# Sheet2.net
KiCad netlist of a schematic drawn in Altium Designer
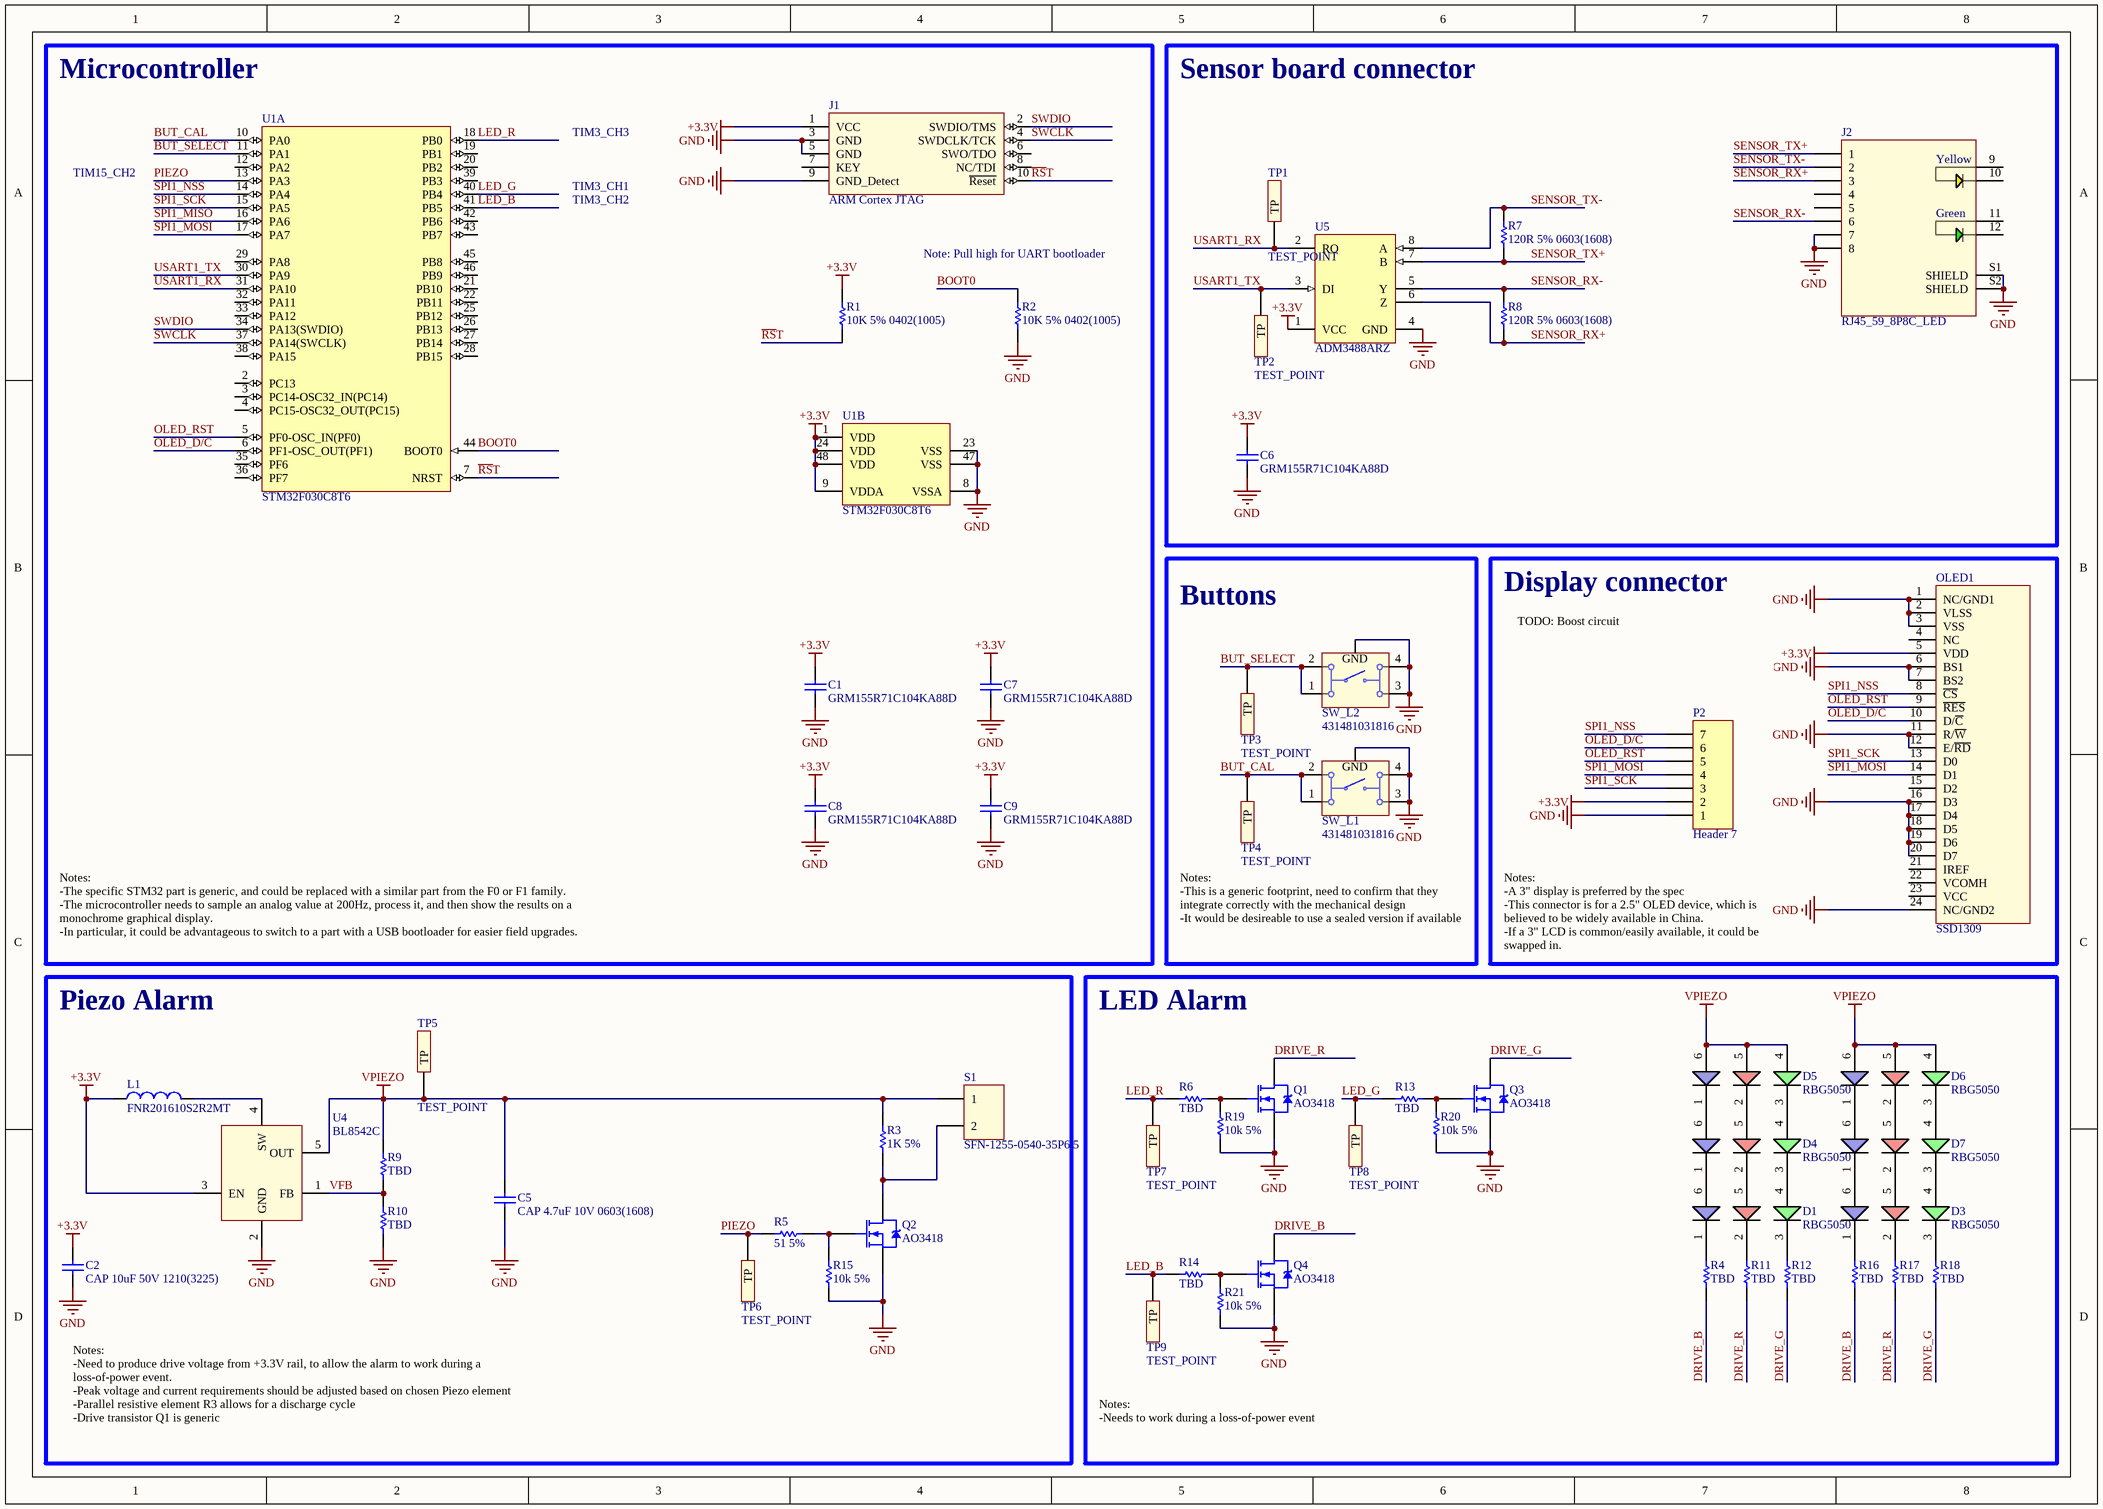
[diagram p0: Sheet2.SchDoc]

(export (version "E")
  (design (tool "Eeschema 10.0.6"))
  (components
    (comp (ref "C1")
      (value "GRM155R71C104KA88D")
      (footprint "CAPC1005X55X25ML05T10")
      (description "Chip Capacitor, 0.1 uF, +/- 10%, 16 V, -55 to 125 degC, 0402 (1005 Metric), RoHS, Tape and Reel")
      (fields (field (name "VOLTAGE") "16V") (field (name "TOLERANCE") "10%"))
      (libsource (lib "Altium Content Vault") (part "CAP-NP-2"))
    )
    (comp (ref "C2")
      (value "CAP 10uF 50V 1210(3225)")
      (footprint "CAPC1210(3225)190_N")
      (description "CAP 10uF 50V -20% to +80% 1210 (3225 Metric) Thickness 1.9mm SMD")
      (fields (field (name "TOLERANCE") "-20% to +80%"))
      (libsource (lib "Altium Content Vault") (part "CAP"))
    )
    (comp (ref "C5")
      (value "CAP 4.7uF 10V 0603(1608)")
      (footprint "CAPC0603(1608)55_L")
      (description "CAP 4.7uF 10V ±10% 0603 (1608 Metric) Thickness 0.55mm SMD")
      (fields (field (name "TOLERANCE") "Â±10%"))
      (libsource (lib "Altium Content Vault") (part "CAP"))
    )
    (comp (ref "C6")
      (value "GRM155R71C104KA88D")
      (footprint "CAPC1005X55X25ML05T10")
      (description "Chip Capacitor, 0.1 uF, +/- 10%, 16 V, -55 to 125 degC, 0402 (1005 Metric), RoHS, Tape and Reel")
      (fields (field (name "VOLTAGE") "16V") (field (name "TOLERANCE") "10%"))
      (libsource (lib "Altium Content Vault") (part "CAP-NP-2"))
    )
    (comp (ref "C7")
      (value "GRM155R71C104KA88D")
      (footprint "CAPC1005X55X25ML05T10")
      (description "Chip Capacitor, 0.1 uF, +/- 10%, 16 V, -55 to 125 degC, 0402 (1005 Metric), RoHS, Tape and Reel")
      (fields (field (name "VOLTAGE") "16V") (field (name "TOLERANCE") "10%"))
      (libsource (lib "Altium Content Vault") (part "CAP-NP-2"))
    )
    (comp (ref "C8")
      (value "GRM155R71C104KA88D")
      (footprint "CAPC1005X55X25ML05T10")
      (description "Chip Capacitor, 0.1 uF, +/- 10%, 16 V, -55 to 125 degC, 0402 (1005 Metric), RoHS, Tape and Reel")
      (fields (field (name "VOLTAGE") "16V") (field (name "TOLERANCE") "10%"))
      (libsource (lib "Altium Content Vault") (part "CAP-NP-2"))
    )
    (comp (ref "C9")
      (value "GRM155R71C104KA88D")
      (footprint "CAPC1005X55X25ML05T10")
      (description "Chip Capacitor, 0.1 uF, +/- 10%, 16 V, -55 to 125 degC, 0402 (1005 Metric), RoHS, Tape and Reel")
      (fields (field (name "VOLTAGE") "16V") (field (name "TOLERANCE") "10%"))
      (libsource (lib "Altium Content Vault") (part "CAP-NP-2"))
    )
    (comp (ref "D1")
      (value "RBG5050")
      (footprint "5050RGB")
      (description "Generic RGB LED in 5050 package. Note that several variants exist, so check the pinout!")
      (fields (field (name "PARTNUMBER") "Unknown/Generic"))
      (libsource (lib "Blinkinlabs") (part "RBG5050"))
    )
    (comp (ref "D3")
      (value "RBG5050")
      (footprint "5050RGB")
      (description "Generic RGB LED in 5050 package. Note that several variants exist, so check the pinout!")
      (fields (field (name "PARTNUMBER") "Unknown/Generic"))
      (libsource (lib "Blinkinlabs") (part "RBG5050"))
    )
    (comp (ref "D4")
      (value "RBG5050")
      (footprint "5050RGB")
      (description "Generic RGB LED in 5050 package. Note that several variants exist, so check the pinout!")
      (fields (field (name "PARTNUMBER") "Unknown/Generic"))
      (libsource (lib "Blinkinlabs") (part "RBG5050"))
    )
    (comp (ref "D5")
      (value "RBG5050")
      (footprint "5050RGB")
      (description "Generic RGB LED in 5050 package. Note that several variants exist, so check the pinout!")
      (fields (field (name "PARTNUMBER") "Unknown/Generic"))
      (libsource (lib "Blinkinlabs") (part "RBG5050"))
    )
    (comp (ref "D6")
      (value "RBG5050")
      (footprint "5050RGB")
      (description "Generic RGB LED in 5050 package. Note that several variants exist, so check the pinout!")
      (fields (field (name "PARTNUMBER") "Unknown/Generic"))
      (libsource (lib "Blinkinlabs") (part "RBG5050"))
    )
    (comp (ref "D7")
      (value "RBG5050")
      (footprint "5050RGB")
      (description "Generic RGB LED in 5050 package. Note that several variants exist, so check the pinout!")
      (fields (field (name "PARTNUMBER") "Unknown/Generic"))
      (libsource (lib "Blinkinlabs") (part "RBG5050"))
    )
    (comp (ref "J1")
      (value "ARM Cortex JTAG")
      (footprint "1.27mm 2x5 SMD Header")
      (description "Arm Cortex 10-pin JTAG connector")
      (fields (field (name "MANUFACTURER") "Unknown/Generic") (field (name "PARTNUMBER") "unknown/Generic"))
      (libsource (lib "Blinkinlabs") (part "ARM Cortex JTAG"))
    )
    (comp (ref "J2")
      (value "RJ45_59_8P8C_LED")
      (footprint "RJ45_59_8P8C_LED")
      (description "Generic RJ49 jack with LED and without magnetics")
      (fields (field (name "MANUFACTURER") "Unknown/Generic"))
      (libsource (lib "Blinkinlabs") (part "RJ45_59_8P8C_LED"))
    )
    (comp (ref "L1")
      (value "FNR201610S2R2MT")
      (footprint "FNR201610S")
      (description "Wire Wound SMD Power Inductors 2.0×1.6×1.0 2.2uH")
      (libsource (lib "Blinkinlabs") (part "FNR201610S2R2MT"))
    )
    (comp (ref "OLED1")
      (value "SSD1309")
      (description "2.4\" OLED display, 24-pin connector, SSD1309 driver IC")
      (libsource (lib "Blinkinlabs") (part "SSD1309"))
    )
    (comp (ref "P2")
      (value "Header 7")
      (footprint "HDR1X7")
      (description "Header, 7-Pin")
      (fields (field (name "PUBLISHER") "Altium Limited"))
      (libsource (lib "Miscellaneous Connectors") (part "Header 7"))
    )
    (comp (ref "Q1")
      (value "AO3418")
      (footprint "SOT95P280X125-3N")
      (description "30V N-Channel MOSFET")
      (fields (field (name "MANUFACTURER") "Alpha & Omega"))
      (libsource (lib "Blinkinlabs") (part "AO3418"))
    )
    (comp (ref "Q2")
      (value "AO3418")
      (footprint "SOT95P280X125-3N")
      (description "30V N-Channel MOSFET")
      (fields (field (name "MANUFACTURER") "Alpha & Omega"))
      (libsource (lib "Blinkinlabs") (part "AO3418"))
    )
    (comp (ref "Q3")
      (value "AO3418")
      (footprint "SOT95P280X125-3N")
      (description "30V N-Channel MOSFET")
      (fields (field (name "MANUFACTURER") "Alpha & Omega"))
      (libsource (lib "Blinkinlabs") (part "AO3418"))
    )
    (comp (ref "Q4")
      (value "AO3418")
      (footprint "SOT95P280X125-3N")
      (description "30V N-Channel MOSFET")
      (fields (field (name "MANUFACTURER") "Alpha & Omega"))
      (libsource (lib "Blinkinlabs") (part "AO3418"))
    )
    (comp (ref "R1")
      (value "10K 5% 0402(1005)")
      (footprint "RESC0402(1005)_N")
      (description "10K 0.063W 5% 0402 (1005 Metric)  SMD")
      (fields (field (name "TOLERANCE") "5 %") (field (name "POWER") "0.063 W"))
      (libsource (lib "Altium Content Vault") (part "RES"))
    )
    (comp (ref "R2")
      (value "10K 5% 0402(1005)")
      (footprint "RESC0402(1005)_N")
      (description "10K 0.063W 5% 0402 (1005 Metric)  SMD")
      (fields (field (name "TOLERANCE") "5 %") (field (name "POWER") "0.063 W"))
      (libsource (lib "Altium Content Vault") (part "RES"))
    )
    (comp (ref "R3")
      (value "1K 5%")
      (footprint "RESC0402(1005)_N")
      (description "10K 0.063W 5% 0402 (1005 Metric)  SMD")
      (fields (field (name "TOLERANCE") "5 %") (field (name "POWER") "0.063 W"))
      (libsource (lib "Altium Content Vault") (part "RES"))
    )
    (comp (ref "R4")
      (value "TBD")
      (footprint "RESC0402(1005)_N")
      (description "10K 0.063W 5% 0402 (1005 Metric)  SMD")
      (fields (field (name "TOLERANCE") "5 %") (field (name "POWER") "0.063 W"))
      (libsource (lib "Altium Content Vault") (part "RES"))
    )
    (comp (ref "R5")
      (value "51 5%")
      (footprint "RESC0402(1005)_N")
      (description "10K 0.063W 5% 0402 (1005 Metric)  SMD")
      (fields (field (name "TOLERANCE") "5 %") (field (name "POWER") "0.063 W"))
      (libsource (lib "Altium Content Vault") (part "RES"))
    )
    (comp (ref "R6")
      (value "TBD")
      (footprint "RESC0402(1005)_N")
      (description "10K 0.063W 5% 0402 (1005 Metric)  SMD")
      (fields (field (name "TOLERANCE") "5 %") (field (name "POWER") "0.063 W"))
      (libsource (lib "Altium Content Vault") (part "RES"))
    )
    (comp (ref "R7")
      (value "120R 5% 0603(1608)")
      (footprint "RESC0603(1608)_L")
      (description "120R 0.1W 5% 0603 (1608 Metric)  SMD")
      (fields (field (name "POWER") "0.1 W") (field (name "TOLERANCE") "5 %"))
      (libsource (lib "Altium Content Vault") (part "RES"))
    )
    (comp (ref "R8")
      (value "120R 5% 0603(1608)")
      (footprint "RESC0603(1608)_L")
      (description "120R 0.1W 5% 0603 (1608 Metric)  SMD")
      (fields (field (name "POWER") "0.1 W") (field (name "TOLERANCE") "5 %"))
      (libsource (lib "Altium Content Vault") (part "RES"))
    )
    (comp (ref "R9")
      (value "TBD")
      (footprint "RESC0402(1005)_N")
      (description "10K 0.063W 5% 0402 (1005 Metric)  SMD")
      (fields (field (name "TOLERANCE") "5 %") (field (name "POWER") "0.063 W"))
      (libsource (lib "Altium Content Vault") (part "RES"))
    )
    (comp (ref "R10")
      (value "TBD")
      (footprint "RESC0402(1005)_N")
      (description "10K 0.063W 5% 0402 (1005 Metric)  SMD")
      (fields (field (name "TOLERANCE") "5 %") (field (name "POWER") "0.063 W"))
      (libsource (lib "Altium Content Vault") (part "RES"))
    )
    (comp (ref "R11")
      (value "TBD")
      (footprint "RESC0402(1005)_N")
      (description "10K 0.063W 5% 0402 (1005 Metric)  SMD")
      (fields (field (name "TOLERANCE") "5 %") (field (name "POWER") "0.063 W"))
      (libsource (lib "Altium Content Vault") (part "RES"))
    )
    (comp (ref "R12")
      (value "TBD")
      (footprint "RESC0402(1005)_N")
      (description "10K 0.063W 5% 0402 (1005 Metric)  SMD")
      (fields (field (name "TOLERANCE") "5 %") (field (name "POWER") "0.063 W"))
      (libsource (lib "Altium Content Vault") (part "RES"))
    )
    (comp (ref "R13")
      (value "TBD")
      (footprint "RESC0402(1005)_N")
      (description "10K 0.063W 5% 0402 (1005 Metric)  SMD")
      (fields (field (name "TOLERANCE") "5 %") (field (name "POWER") "0.063 W"))
      (libsource (lib "Altium Content Vault") (part "RES"))
    )
    (comp (ref "R14")
      (value "TBD")
      (footprint "RESC0402(1005)_N")
      (description "10K 0.063W 5% 0402 (1005 Metric)  SMD")
      (fields (field (name "TOLERANCE") "5 %") (field (name "POWER") "0.063 W"))
      (libsource (lib "Altium Content Vault") (part "RES"))
    )
    (comp (ref "R15")
      (value "10k 5%")
      (footprint "RESC0402(1005)_N")
      (description "10K 0.063W 5% 0402 (1005 Metric)  SMD")
      (fields (field (name "TOLERANCE") "5 %") (field (name "POWER") "0.063 W"))
      (libsource (lib "Altium Content Vault") (part "RES"))
    )
    (comp (ref "R16")
      (value "TBD")
      (footprint "RESC0402(1005)_N")
      (description "10K 0.063W 5% 0402 (1005 Metric)  SMD")
      (fields (field (name "TOLERANCE") "5 %") (field (name "POWER") "0.063 W"))
      (libsource (lib "Altium Content Vault") (part "RES"))
    )
    (comp (ref "R17")
      (value "TBD")
      (footprint "RESC0402(1005)_N")
      (description "10K 0.063W 5% 0402 (1005 Metric)  SMD")
      (fields (field (name "TOLERANCE") "5 %") (field (name "POWER") "0.063 W"))
      (libsource (lib "Altium Content Vault") (part "RES"))
    )
    (comp (ref "R18")
      (value "TBD")
      (footprint "RESC0402(1005)_N")
      (description "10K 0.063W 5% 0402 (1005 Metric)  SMD")
      (fields (field (name "TOLERANCE") "5 %") (field (name "POWER") "0.063 W"))
      (libsource (lib "Altium Content Vault") (part "RES"))
    )
    (comp (ref "R19")
      (value "10k 5%")
      (footprint "RESC0402(1005)_N")
      (description "10K 0.063W 5% 0402 (1005 Metric)  SMD")
      (fields (field (name "TOLERANCE") "5 %") (field (name "POWER") "0.063 W"))
      (libsource (lib "Altium Content Vault") (part "RES"))
    )
    (comp (ref "R20")
      (value "10k 5%")
      (footprint "RESC0402(1005)_N")
      (description "10K 0.063W 5% 0402 (1005 Metric)  SMD")
      (fields (field (name "TOLERANCE") "5 %") (field (name "POWER") "0.063 W"))
      (libsource (lib "Altium Content Vault") (part "RES"))
    )
    (comp (ref "R21")
      (value "10k 5%")
      (footprint "RESC0402(1005)_N")
      (description "10K 0.063W 5% 0402 (1005 Metric)  SMD")
      (fields (field (name "TOLERANCE") "5 %") (field (name "POWER") "0.063 W"))
      (libsource (lib "Altium Content Vault") (part "RES"))
    )
    (comp (ref "S1")
      (value "SFN-1255-0540-35P6.5")
      (footprint "SFN-1255-0540-35P6.5")
      (description "Piezo Buzzer, 4KHz")
      (fields (field (name "MANUFACTURER") "S&S"))
      (libsource (lib "Blinkinlabs") (part "SFN-1255-0540-35P6.5"))
    )
    (comp (ref "SW_L1")
      (value "431481031816")
      (footprint "431481031816")
      (description "WS-TASV SMD Tact Switch 6X6 mm with ground terminal")
      (fields (field (name "MANUFACTURER") "Wuerth Elektronik"))
      (libsource (lib "Altium Content Vault") (part "WE-TACT-SW-5"))
    )
    (comp (ref "SW_L2")
      (value "431481031816")
      (footprint "431481031816")
      (description "WS-TASV SMD Tact Switch 6X6 mm with ground terminal")
      (fields (field (name "MANUFACTURER") "Wuerth Elektronik"))
      (libsource (lib "Altium Content Vault") (part "WE-TACT-SW-5"))
    )
    (comp (ref "TP1")
      (value "TEST_POINT")
      (footprint "TP-SMD-1mm")
      (description "Test point")
      (libsource (lib "") (part "TEST_POINT_1"))
    )
    (comp (ref "TP2")
      (value "TEST_POINT")
      (footprint "TP-SMD-1mm")
      (description "Test point")
      (libsource (lib "Blinkinlabs") (part "TEST_POINT"))
    )
    (comp (ref "TP3")
      (value "TEST_POINT")
      (footprint "TP-SMD-1mm")
      (description "Test point")
      (libsource (lib "Blinkinlabs") (part "TEST_POINT"))
    )
    (comp (ref "TP4")
      (value "TEST_POINT")
      (footprint "TP-SMD-1mm")
      (description "Test point")
      (libsource (lib "Blinkinlabs") (part "TEST_POINT"))
    )
    (comp (ref "TP5")
      (value "TEST_POINT")
      (footprint "TP-SMD-1mm")
      (description "Test point")
      (libsource (lib "") (part "TEST_POINT_1"))
    )
    (comp (ref "TP6")
      (value "TEST_POINT")
      (footprint "TP-SMD-1mm")
      (description "Test point")
      (libsource (lib "Blinkinlabs") (part "TEST_POINT"))
    )
    (comp (ref "TP7")
      (value "TEST_POINT")
      (footprint "TP-SMD-1mm")
      (description "Test point")
      (libsource (lib "Blinkinlabs") (part "TEST_POINT"))
    )
    (comp (ref "TP8")
      (value "TEST_POINT")
      (footprint "TP-SMD-1mm")
      (description "Test point")
      (libsource (lib "Blinkinlabs") (part "TEST_POINT"))
    )
    (comp (ref "TP9")
      (value "TEST_POINT")
      (footprint "TP-SMD-1mm")
      (description "Test point")
      (libsource (lib "Blinkinlabs") (part "TEST_POINT"))
    )
    (comp (ref "U1")
      (value "STM32F030C8T6")
      (footprint "STM-LQFP48_M")
      (libsource (lib "Altium Content Vault") (part "MC-ARM-STM32F030_X8-SQ48"))
    )
    (comp (ref "U4")
      (value "BL8542C")
      (footprint "SOT95P280X130-5N")
      (description "0.85V startup, 1MHz, 300mA Iout,  Synchronous Boost Converter (adjustable output)")
      (fields (field (name "MANUFACTURER") "Belling"))
      (libsource (lib "Blinkinlabs") (part "BL8542C"))
    )
    (comp (ref "U5")
      (value "ADM3488ARZ")
      (footprint "ADI-R-8_L")
      (fields (field (name "MANUFACTURER") "Analog Devices"))
      (libsource (lib "Altium Content Vault") (part "ADI-ADM3488_90-R-8"))
    )
  )
  (nets
    (net (code "1") (name "+3.3V") (class "Default")
      (node (ref "C1") (pin "2") (pinfunction "2_2") (pintype "passive"))
      (node (ref "C2") (pin "2") (pinfunction "2_2") (pintype "passive"))
      (node (ref "C6") (pin "2") (pinfunction "2_2") (pintype "passive"))
      (node (ref "C7") (pin "2") (pinfunction "2_2") (pintype "passive"))
      (node (ref "C8") (pin "2") (pinfunction "2_2") (pintype "passive"))
      (node (ref "C9") (pin "2") (pinfunction "2_2") (pintype "passive"))
      (node (ref "J1") (pin "1") (pinfunction "VCC_1") (pintype "power_in"))
      (node (ref "L1") (pin "1") (pinfunction "1_1") (pintype "passive"))
      (node (ref "OLED1") (pin "5") (pinfunction "VDD_5") (pintype "passive"))
      (node (ref "P2") (pin "2") (pinfunction "2_2") (pintype "passive"))
      (node (ref "R1") (pin "1") (pinfunction "1_1") (pintype "passive"))
      (node (ref "U1") (pin "1") (pinfunction "VDD_1") (pintype "power_in"))
      (node (ref "U1") (pin "24") (pinfunction "VDD_24") (pintype "power_in"))
      (node (ref "U1") (pin "48") (pinfunction "VDD_48") (pintype "power_in"))
      (node (ref "U1") (pin "9") (pinfunction "VDDA_9") (pintype "power_in"))
      (node (ref "U4") (pin "3") (pinfunction "EN_3") (pintype "passive"))
      (node (ref "U5") (pin "1") (pinfunction "VCC_1") (pintype "power_in"))
    )
    (net (code "2") (name "/BOOT0") (class "Default")
      (node (ref "R2") (pin "1") (pinfunction "1_1") (pintype "passive"))
      (node (ref "U1") (pin "44") (pinfunction "BOOT0_44") (pintype "input"))
    )
    (net (code "3") (name "/BUT_CAL") (class "Default")
      (node (ref "SW_L1") (pin "1") (pinfunction "1_1") (pintype "passive"))
      (node (ref "SW_L1") (pin "2") (pinfunction "2_2") (pintype "passive"))
      (node (ref "TP4") (pin "1") (pinfunction "TP_1") (pintype "passive"))
      (node (ref "U1") (pin "10") (pinfunction "PA0_10") (pintype "bidirectional"))
    )
    (net (code "4") (name "/BUT_SELECT") (class "Default")
      (node (ref "SW_L2") (pin "1") (pinfunction "1_1") (pintype "passive"))
      (node (ref "SW_L2") (pin "2") (pinfunction "2_2") (pintype "passive"))
      (node (ref "TP3") (pin "1") (pinfunction "TP_1") (pintype "passive"))
      (node (ref "U1") (pin "11") (pinfunction "PA1_11") (pintype "bidirectional"))
    )
    (net (code "5") (name "/DRIVE_B") (class "Default")
      (node (ref "Q4") (pin "3") (pinfunction "DRAIN_3") (pintype "passive"))
      (node (ref "R16") (pin "1") (pinfunction "1_1") (pintype "passive"))
      (node (ref "R4") (pin "1") (pinfunction "1_1") (pintype "passive"))
    )
    (net (code "6") (name "/DRIVE_G") (class "Default")
      (node (ref "Q3") (pin "3") (pinfunction "DRAIN_3") (pintype "passive"))
      (node (ref "R12") (pin "1") (pinfunction "1_1") (pintype "passive"))
      (node (ref "R18") (pin "1") (pinfunction "1_1") (pintype "passive"))
    )
    (net (code "7") (name "/DRIVE_R") (class "Default")
      (node (ref "Q1") (pin "3") (pinfunction "DRAIN_3") (pintype "passive"))
      (node (ref "R11") (pin "1") (pinfunction "1_1") (pintype "passive"))
      (node (ref "R17") (pin "1") (pinfunction "1_1") (pintype "passive"))
    )
    (net (code "8") (name "/LED_B") (class "Default")
      (node (ref "R14") (pin "1") (pinfunction "1_1") (pintype "passive"))
      (node (ref "TP9") (pin "1") (pinfunction "TP_1") (pintype "passive"))
      (node (ref "U1") (pin "41") (pinfunction "PB5_41") (pintype "bidirectional"))
    )
    (net (code "9") (name "/LED_G") (class "Default")
      (node (ref "R13") (pin "1") (pinfunction "1_1") (pintype "passive"))
      (node (ref "TP8") (pin "1") (pinfunction "TP_1") (pintype "passive"))
      (node (ref "U1") (pin "40") (pinfunction "PB4_40") (pintype "bidirectional"))
    )
    (net (code "10") (name "/LED_R") (class "Default")
      (node (ref "R6") (pin "1") (pinfunction "1_1") (pintype "passive"))
      (node (ref "TP7") (pin "1") (pinfunction "TP_1") (pintype "passive"))
      (node (ref "U1") (pin "18") (pinfunction "PB0_18") (pintype "bidirectional"))
    )
    (net (code "11") (name "/OLED_D{slash}C") (class "Default")
      (node (ref "OLED1") (pin "10") (pinfunction "D/~{C}_10") (pintype "passive"))
      (node (ref "P2") (pin "6") (pinfunction "6_6") (pintype "passive"))
      (node (ref "U1") (pin "6") (pinfunction "PF1-OSC_OUT(PF1)_6") (pintype "bidirectional"))
    )
    (net (code "12") (name "/OLED_RST") (class "Default")
      (node (ref "OLED1") (pin "9") (pinfunction "~{RES}_9") (pintype "passive"))
      (node (ref "P2") (pin "5") (pinfunction "5_5") (pintype "passive"))
      (node (ref "U1") (pin "5") (pinfunction "PF0-OSC_IN(PF0)_5") (pintype "bidirectional"))
    )
    (net (code "13") (name "/PIEZO") (class "Default")
      (node (ref "R5") (pin "1") (pinfunction "1_1") (pintype "passive"))
      (node (ref "TP6") (pin "1") (pinfunction "TP_1") (pintype "passive"))
      (node (ref "U1") (pin "13") (pinfunction "PA3_13") (pintype "bidirectional"))
    )
    (net (code "14") (name "/SENSOR_RX+") (class "Default")
      (node (ref "J2") (pin "3") (pinfunction "3_3") (pintype "passive"))
      (node (ref "R8") (pin "1") (pinfunction "1_1") (pintype "passive"))
      (node (ref "U5") (pin "6") (pinfunction "Z_6") (pintype "tri_state"))
    )
    (net (code "15") (name "/SENSOR_RX-") (class "Default")
      (node (ref "J2") (pin "6") (pinfunction "6_6") (pintype "passive"))
      (node (ref "R8") (pin "2") (pinfunction "2_2") (pintype "passive"))
      (node (ref "U5") (pin "5") (pinfunction "Y_5") (pintype "tri_state"))
    )
    (net (code "16") (name "/SENSOR_TX+") (class "Default")
      (node (ref "J2") (pin "1") (pinfunction "1_1") (pintype "passive"))
      (node (ref "R7") (pin "1") (pinfunction "1_1") (pintype "passive"))
      (node (ref "U5") (pin "7") (pinfunction "B_7") (pintype "input"))
    )
    (net (code "17") (name "/SENSOR_TX-") (class "Default")
      (node (ref "J2") (pin "2") (pinfunction "2_2") (pintype "passive"))
      (node (ref "R7") (pin "2") (pinfunction "2_2") (pintype "passive"))
      (node (ref "U5") (pin "8") (pinfunction "A_8") (pintype "input"))
    )
    (net (code "18") (name "/SPI1_MISO") (class "Default")
      (node (ref "U1") (pin "16") (pinfunction "PA6_16") (pintype "bidirectional"))
    )
    (net (code "19") (name "/SPI1_MOSI") (class "Default")
      (node (ref "OLED1") (pin "14") (pinfunction "D1_14") (pintype "passive"))
      (node (ref "P2") (pin "4") (pinfunction "4_4") (pintype "passive"))
      (node (ref "U1") (pin "17") (pinfunction "PA7_17") (pintype "bidirectional"))
    )
    (net (code "20") (name "/SPI1_NSS") (class "Default")
      (node (ref "OLED1") (pin "8") (pinfunction "~{CS}_8") (pintype "passive"))
      (node (ref "P2") (pin "7") (pinfunction "7_7") (pintype "passive"))
      (node (ref "U1") (pin "14") (pinfunction "PA4_14") (pintype "bidirectional"))
    )
    (net (code "21") (name "/SPI1_SCK") (class "Default")
      (node (ref "OLED1") (pin "13") (pinfunction "D0_13") (pintype "passive"))
      (node (ref "P2") (pin "3") (pinfunction "3_3") (pintype "passive"))
      (node (ref "U1") (pin "15") (pinfunction "PA5_15") (pintype "bidirectional"))
    )
    (net (code "22") (name "/SWCLK") (class "Default")
      (node (ref "J1") (pin "4") (pinfunction "SWDCLK/TCK_4") (pintype "bidirectional"))
      (node (ref "U1") (pin "37") (pinfunction "PA14(SWCLK)_37") (pintype "bidirectional"))
    )
    (net (code "23") (name "/SWDIO") (class "Default")
      (node (ref "J1") (pin "2") (pinfunction "SWDIO/TMS_2") (pintype "bidirectional"))
      (node (ref "U1") (pin "34") (pinfunction "PA13(SWDIO)_34") (pintype "bidirectional"))
    )
    (net (code "24") (name "/USART1_RX") (class "Default")
      (node (ref "TP1") (pin "1") (pinfunction "TP_1") (pintype "passive"))
      (node (ref "U1") (pin "31") (pinfunction "PA10_31") (pintype "bidirectional"))
      (node (ref "U5") (pin "2") (pinfunction "RO_2") (pintype "tri_state"))
    )
    (net (code "25") (name "/USART1_TX") (class "Default")
      (node (ref "TP2") (pin "1") (pinfunction "TP_1") (pintype "passive"))
      (node (ref "U1") (pin "30") (pinfunction "PA9_30") (pintype "bidirectional"))
      (node (ref "U5") (pin "3") (pinfunction "DI_3") (pintype "input"))
    )
    (net (code "26") (name "/VFB") (class "Default")
      (node (ref "R10") (pin "2") (pinfunction "2_2") (pintype "passive"))
      (node (ref "R9") (pin "1") (pinfunction "1_1") (pintype "passive"))
      (node (ref "U4") (pin "1") (pinfunction "FB_1") (pintype "passive"))
    )
    (net (code "27") (name "/~{RS}T") (class "Default")
      (node (ref "J1") (pin "10") (pinfunction "~{Reset}_10") (pintype "bidirectional"))
      (node (ref "R1") (pin "2") (pinfunction "2_2") (pintype "passive"))
      (node (ref "U1") (pin "7") (pinfunction "NRST_7") (pintype "bidirectional"))
    )
    (net (code "28") (name "GND") (class "Default")
      (node (ref "C1") (pin "1") (pinfunction "1_1") (pintype "passive"))
      (node (ref "C2") (pin "1") (pinfunction "1_1") (pintype "passive"))
      (node (ref "C5") (pin "1") (pinfunction "1_1") (pintype "passive"))
      (node (ref "C6") (pin "1") (pinfunction "1_1") (pintype "passive"))
      (node (ref "C7") (pin "1") (pinfunction "1_1") (pintype "passive"))
      (node (ref "C8") (pin "1") (pinfunction "1_1") (pintype "passive"))
      (node (ref "C9") (pin "1") (pinfunction "1_1") (pintype "passive"))
      (node (ref "J1") (pin "3") (pinfunction "GND_3") (pintype "power_in"))
      (node (ref "J1") (pin "5") (pinfunction "GND_5") (pintype "power_in"))
      (node (ref "J1") (pin "9") (pinfunction "GND_Detect_9") (pintype "power_in"))
      (node (ref "J2") (pin "7") (pinfunction "7_7") (pintype "passive"))
      (node (ref "J2") (pin "8") (pinfunction "8_8") (pintype "passive"))
      (node (ref "J2") (pin "S1") (pinfunction "SHIELD_S1") (pintype "passive"))
      (node (ref "J2") (pin "S2") (pinfunction "SHIELD_S2") (pintype "passive"))
      (node (ref "OLED1") (pin "1") (pinfunction "NC/GND1_1") (pintype "power_in"))
      (node (ref "OLED1") (pin "11") (pinfunction "R/~{W}_11") (pintype "passive"))
      (node (ref "OLED1") (pin "12") (pinfunction "E/~{RD}_12") (pintype "passive"))
      (node (ref "OLED1") (pin "16") (pinfunction "D3_16") (pintype "passive"))
      (node (ref "OLED1") (pin "17") (pinfunction "D4_17") (pintype "passive"))
      (node (ref "OLED1") (pin "18") (pinfunction "D5_18") (pintype "passive"))
      (node (ref "OLED1") (pin "19") (pinfunction "D6_19") (pintype "passive"))
      (node (ref "OLED1") (pin "2") (pinfunction "VLSS_2") (pintype "passive"))
      (node (ref "OLED1") (pin "20") (pinfunction "D7_20") (pintype "passive"))
      (node (ref "OLED1") (pin "24") (pinfunction "NC/GND2_24") (pintype "passive"))
      (node (ref "OLED1") (pin "3") (pinfunction "VSS_3") (pintype "passive"))
      (node (ref "OLED1") (pin "6") (pinfunction "BS1_6") (pintype "passive"))
      (node (ref "OLED1") (pin "7") (pinfunction "BS2_7") (pintype "passive"))
      (node (ref "P2") (pin "1") (pinfunction "1_1") (pintype "passive"))
      (node (ref "Q1") (pin "2") (pinfunction "SOURCE_2") (pintype "passive"))
      (node (ref "Q2") (pin "2") (pinfunction "SOURCE_2") (pintype "passive"))
      (node (ref "Q3") (pin "2") (pinfunction "SOURCE_2") (pintype "passive"))
      (node (ref "Q4") (pin "2") (pinfunction "SOURCE_2") (pintype "passive"))
      (node (ref "R10") (pin "1") (pinfunction "1_1") (pintype "passive"))
      (node (ref "R15") (pin "1") (pinfunction "1_1") (pintype "passive"))
      (node (ref "R19") (pin "1") (pinfunction "1_1") (pintype "passive"))
      (node (ref "R2") (pin "2") (pinfunction "2_2") (pintype "passive"))
      (node (ref "R20") (pin "1") (pinfunction "1_1") (pintype "passive"))
      (node (ref "R21") (pin "1") (pinfunction "1_1") (pintype "passive"))
      (node (ref "SW_L1") (pin "3") (pinfunction "3_3") (pintype "passive"))
      (node (ref "SW_L1") (pin "4") (pinfunction "4_4") (pintype "passive"))
      (node (ref "SW_L1") (pin "5") (pinfunction "5_5") (pintype "passive"))
      (node (ref "SW_L2") (pin "3") (pinfunction "3_3") (pintype "passive"))
      (node (ref "SW_L2") (pin "4") (pinfunction "4_4") (pintype "passive"))
      (node (ref "SW_L2") (pin "5") (pinfunction "5_5") (pintype "passive"))
      (node (ref "U1") (pin "23") (pinfunction "VSS_23") (pintype "power_in"))
      (node (ref "U1") (pin "47") (pinfunction "VSS_47") (pintype "power_in"))
      (node (ref "U1") (pin "8") (pinfunction "VSSA_8") (pintype "power_in"))
      (node (ref "U4") (pin "2") (pinfunction "GND_2") (pintype "passive"))
      (node (ref "U5") (pin "4") (pinfunction "GND_4") (pintype "power_in"))
    )
    (net (code "29") (name "Net-(D1-Pad1)") (class "Default")
      (node (ref "D1") (pin "1") (pinfunction "1_1") (pintype "passive"))
      (node (ref "R4") (pin "2") (pinfunction "2_2") (pintype "passive"))
    )
    (net (code "30") (name "Net-(D1-Pad2)") (class "Default")
      (node (ref "D1") (pin "2") (pinfunction "2_2") (pintype "passive"))
      (node (ref "R11") (pin "2") (pinfunction "2_2") (pintype "passive"))
    )
    (net (code "31") (name "Net-(D1-Pad3)") (class "Default")
      (node (ref "D1") (pin "3") (pinfunction "3_3") (pintype "passive"))
      (node (ref "R12") (pin "2") (pinfunction "2_2") (pintype "passive"))
    )
    (net (code "32") (name "Net-(D1-Pad4)") (class "Default")
      (node (ref "D1") (pin "4") (pinfunction "4_4") (pintype "passive"))
      (node (ref "D4") (pin "3") (pinfunction "3_3") (pintype "passive"))
    )
    (net (code "33") (name "Net-(D1-Pad5)") (class "Default")
      (node (ref "D1") (pin "5") (pinfunction "5_5") (pintype "passive"))
      (node (ref "D4") (pin "2") (pinfunction "2_2") (pintype "passive"))
    )
    (net (code "34") (name "Net-(D1-Pad6)") (class "Default")
      (node (ref "D1") (pin "6") (pinfunction "6_6") (pintype "passive"))
      (node (ref "D4") (pin "1") (pinfunction "1_1") (pintype "passive"))
    )
    (net (code "35") (name "Net-(D3-Pad1)") (class "Default")
      (node (ref "D3") (pin "1") (pinfunction "1_1") (pintype "passive"))
      (node (ref "R16") (pin "2") (pinfunction "2_2") (pintype "passive"))
    )
    (net (code "36") (name "Net-(D3-Pad2)") (class "Default")
      (node (ref "D3") (pin "2") (pinfunction "2_2") (pintype "passive"))
      (node (ref "R17") (pin "2") (pinfunction "2_2") (pintype "passive"))
    )
    (net (code "37") (name "Net-(D3-Pad3)") (class "Default")
      (node (ref "D3") (pin "3") (pinfunction "3_3") (pintype "passive"))
      (node (ref "R18") (pin "2") (pinfunction "2_2") (pintype "passive"))
    )
    (net (code "38") (name "Net-(D3-Pad4)") (class "Default")
      (node (ref "D3") (pin "4") (pinfunction "4_4") (pintype "passive"))
      (node (ref "D7") (pin "3") (pinfunction "3_3") (pintype "passive"))
    )
    (net (code "39") (name "Net-(D3-Pad5)") (class "Default")
      (node (ref "D3") (pin "5") (pinfunction "5_5") (pintype "passive"))
      (node (ref "D7") (pin "2") (pinfunction "2_2") (pintype "passive"))
    )
    (net (code "40") (name "Net-(D3-Pad6)") (class "Default")
      (node (ref "D3") (pin "6") (pinfunction "6_6") (pintype "passive"))
      (node (ref "D7") (pin "1") (pinfunction "1_1") (pintype "passive"))
    )
    (net (code "41") (name "Net-(D4-Pad4)") (class "Default")
      (node (ref "D4") (pin "4") (pinfunction "4_4") (pintype "passive"))
      (node (ref "D5") (pin "3") (pinfunction "3_3") (pintype "passive"))
    )
    (net (code "42") (name "Net-(D4-Pad5)") (class "Default")
      (node (ref "D4") (pin "5") (pinfunction "5_5") (pintype "passive"))
      (node (ref "D5") (pin "2") (pinfunction "2_2") (pintype "passive"))
    )
    (net (code "43") (name "Net-(D4-Pad6)") (class "Default")
      (node (ref "D4") (pin "6") (pinfunction "6_6") (pintype "passive"))
      (node (ref "D5") (pin "1") (pinfunction "1_1") (pintype "passive"))
    )
    (net (code "44") (name "Net-(D6-Pad1)") (class "Default")
      (node (ref "D6") (pin "1") (pinfunction "1_1") (pintype "passive"))
      (node (ref "D7") (pin "6") (pinfunction "6_6") (pintype "passive"))
    )
    (net (code "45") (name "Net-(D6-Pad2)") (class "Default")
      (node (ref "D6") (pin "2") (pinfunction "2_2") (pintype "passive"))
      (node (ref "D7") (pin "5") (pinfunction "5_5") (pintype "passive"))
    )
    (net (code "46") (name "Net-(D6-Pad3)") (class "Default")
      (node (ref "D6") (pin "3") (pinfunction "3_3") (pintype "passive"))
      (node (ref "D7") (pin "4") (pinfunction "4_4") (pintype "passive"))
    )
    (net (code "47") (name "Net-(Q1-GATE)") (class "Default")
      (node (ref "Q1") (pin "1") (pinfunction "GATE_1") (pintype "passive"))
      (node (ref "R19") (pin "2") (pinfunction "2_2") (pintype "passive"))
      (node (ref "R6") (pin "2") (pinfunction "2_2") (pintype "passive"))
    )
    (net (code "48") (name "Net-(Q2-DRAIN)") (class "Default")
      (node (ref "Q2") (pin "3") (pinfunction "DRAIN_3") (pintype "passive"))
      (node (ref "R3") (pin "1") (pinfunction "1_1") (pintype "passive"))
      (node (ref "S1") (pin "2") (pinfunction "2_2") (pintype "passive"))
    )
    (net (code "49") (name "Net-(Q2-GATE)") (class "Default")
      (node (ref "Q2") (pin "1") (pinfunction "GATE_1") (pintype "passive"))
      (node (ref "R15") (pin "2") (pinfunction "2_2") (pintype "passive"))
      (node (ref "R5") (pin "2") (pinfunction "2_2") (pintype "passive"))
    )
    (net (code "50") (name "Net-(Q3-GATE)") (class "Default")
      (node (ref "Q3") (pin "1") (pinfunction "GATE_1") (pintype "passive"))
      (node (ref "R13") (pin "2") (pinfunction "2_2") (pintype "passive"))
      (node (ref "R20") (pin "2") (pinfunction "2_2") (pintype "passive"))
    )
    (net (code "51") (name "Net-(Q4-GATE)") (class "Default")
      (node (ref "Q4") (pin "1") (pinfunction "GATE_1") (pintype "passive"))
      (node (ref "R14") (pin "2") (pinfunction "2_2") (pintype "passive"))
      (node (ref "R21") (pin "2") (pinfunction "2_2") (pintype "passive"))
    )
    (net (code "52") (name "Net-(U4-SW)") (class "Default")
      (node (ref "L1") (pin "2") (pinfunction "2_2") (pintype "passive"))
      (node (ref "U4") (pin "4") (pinfunction "SW_4") (pintype "passive"))
    )
    (net (code "53") (name "VPIEZO") (class "Default")
      (node (ref "C5") (pin "2") (pinfunction "2_2") (pintype "passive"))
      (node (ref "D5") (pin "4") (pinfunction "4_4") (pintype "passive"))
      (node (ref "D5") (pin "5") (pinfunction "5_5") (pintype "passive"))
      (node (ref "D5") (pin "6") (pinfunction "6_6") (pintype "passive"))
      (node (ref "D6") (pin "4") (pinfunction "4_4") (pintype "passive"))
      (node (ref "D6") (pin "5") (pinfunction "5_5") (pintype "passive"))
      (node (ref "D6") (pin "6") (pinfunction "6_6") (pintype "passive"))
      (node (ref "R3") (pin "2") (pinfunction "2_2") (pintype "passive"))
      (node (ref "R9") (pin "2") (pinfunction "2_2") (pintype "passive"))
      (node (ref "S1") (pin "1") (pinfunction "1_1") (pintype "passive"))
      (node (ref "TP5") (pin "1") (pinfunction "TP_1") (pintype "passive"))
      (node (ref "U4") (pin "5") (pinfunction "OUT_5") (pintype "passive"))
    )
    (net (code "54") (name "unconnected-(J1-KEY-Pad7)") (class "Default")
      (node (ref "J1") (pin "7") (pinfunction "KEY_7") (pintype "passive"))
    )
    (net (code "55") (name "unconnected-(J1-NC{slash}TDI-Pad8)") (class "Default")
      (node (ref "J1") (pin "8") (pinfunction "NC/TDI_8") (pintype "bidirectional"))
    )
    (net (code "56") (name "unconnected-(J1-SWO{slash}TDO-Pad6)") (class "Default")
      (node (ref "J1") (pin "6") (pinfunction "SWO/TDO_6") (pintype "bidirectional"))
    )
    (net (code "57") (name "unconnected-(J2-Green_Anode-Pad11)") (class "Default")
      (node (ref "J2") (pin "11") (pinfunction "Green_Anode_11") (pintype "passive"))
    )
    (net (code "58") (name "unconnected-(J2-Green_Cathode-Pad12)") (class "Default")
      (node (ref "J2") (pin "12") (pinfunction "Green_Cathode_12") (pintype "passive"))
    )
    (net (code "59") (name "unconnected-(J2-Pad4)") (class "Default")
      (node (ref "J2") (pin "4") (pinfunction "4_4") (pintype "passive"))
    )
    (net (code "60") (name "unconnected-(J2-Pad5)") (class "Default")
      (node (ref "J2") (pin "5") (pinfunction "5_5") (pintype "passive"))
    )
    (net (code "61") (name "unconnected-(J2-Yellow_Anode-Pad9)") (class "Default")
      (node (ref "J2") (pin "9") (pinfunction "Yellow_Anode_9") (pintype "passive"))
    )
    (net (code "62") (name "unconnected-(J2-Yellow_Cathode-Pad10)") (class "Default")
      (node (ref "J2") (pin "10") (pinfunction "Yellow_Cathode_10") (pintype "passive"))
    )
    (net (code "63") (name "unconnected-(OLED1-D2-Pad15)") (class "Default")
      (node (ref "OLED1") (pin "15") (pinfunction "D2_15") (pintype "passive"))
    )
    (net (code "64") (name "unconnected-(OLED1-IREF-Pad21)") (class "Default")
      (node (ref "OLED1") (pin "21") (pinfunction "IREF_21") (pintype "passive"))
    )
    (net (code "65") (name "unconnected-(OLED1-NC-Pad4)") (class "Default")
      (node (ref "OLED1") (pin "4") (pinfunction "NC_4") (pintype "passive"))
    )
    (net (code "66") (name "unconnected-(OLED1-VCC-Pad23)") (class "Default")
      (node (ref "OLED1") (pin "23") (pinfunction "VCC_23") (pintype "passive"))
    )
    (net (code "67") (name "unconnected-(OLED1-VCOMH-Pad22)") (class "Default")
      (node (ref "OLED1") (pin "22") (pinfunction "VCOMH_22") (pintype "passive"))
    )
    (net (code "68") (name "unconnected-(U1A-PA2-Pad12)") (class "Default")
      (node (ref "U1") (pin "12") (pinfunction "PA2_12") (pintype "bidirectional"))
    )
    (net (code "69") (name "unconnected-(U1A-PA8-Pad29)") (class "Default")
      (node (ref "U1") (pin "29") (pinfunction "PA8_29") (pintype "bidirectional"))
    )
    (net (code "70") (name "unconnected-(U1A-PA11-Pad32)") (class "Default")
      (node (ref "U1") (pin "32") (pinfunction "PA11_32") (pintype "bidirectional"))
    )
    (net (code "71") (name "unconnected-(U1A-PA12-Pad33)") (class "Default")
      (node (ref "U1") (pin "33") (pinfunction "PA12_33") (pintype "bidirectional"))
    )
    (net (code "72") (name "unconnected-(U1A-PA15-Pad38)") (class "Default")
      (node (ref "U1") (pin "38") (pinfunction "PA15_38") (pintype "bidirectional"))
    )
    (net (code "73") (name "unconnected-(U1A-PB1-Pad19)") (class "Default")
      (node (ref "U1") (pin "19") (pinfunction "PB1_19") (pintype "bidirectional"))
    )
    (net (code "74") (name "unconnected-(U1A-PB2-Pad20)") (class "Default")
      (node (ref "U1") (pin "20") (pinfunction "PB2_20") (pintype "bidirectional"))
    )
    (net (code "75") (name "unconnected-(U1A-PB3-Pad39)") (class "Default")
      (node (ref "U1") (pin "39") (pinfunction "PB3_39") (pintype "bidirectional"))
    )
    (net (code "76") (name "unconnected-(U1A-PB6-Pad42)") (class "Default")
      (node (ref "U1") (pin "42") (pinfunction "PB6_42") (pintype "bidirectional"))
    )
    (net (code "77") (name "unconnected-(U1A-PB7-Pad43)") (class "Default")
      (node (ref "U1") (pin "43") (pinfunction "PB7_43") (pintype "bidirectional"))
    )
    (net (code "78") (name "unconnected-(U1A-PB8-Pad45)") (class "Default")
      (node (ref "U1") (pin "45") (pinfunction "PB8_45") (pintype "bidirectional"))
    )
    (net (code "79") (name "unconnected-(U1A-PB9-Pad46)") (class "Default")
      (node (ref "U1") (pin "46") (pinfunction "PB9_46") (pintype "bidirectional"))
    )
    (net (code "80") (name "unconnected-(U1A-PB10-Pad21)") (class "Default")
      (node (ref "U1") (pin "21") (pinfunction "PB10_21") (pintype "bidirectional"))
    )
    (net (code "81") (name "unconnected-(U1A-PB11-Pad22)") (class "Default")
      (node (ref "U1") (pin "22") (pinfunction "PB11_22") (pintype "bidirectional"))
    )
    (net (code "82") (name "unconnected-(U1A-PB12-Pad25)") (class "Default")
      (node (ref "U1") (pin "25") (pinfunction "PB12_25") (pintype "bidirectional"))
    )
    (net (code "83") (name "unconnected-(U1A-PB13-Pad26)") (class "Default")
      (node (ref "U1") (pin "26") (pinfunction "PB13_26") (pintype "bidirectional"))
    )
    (net (code "84") (name "unconnected-(U1A-PB14-Pad27)") (class "Default")
      (node (ref "U1") (pin "27") (pinfunction "PB14_27") (pintype "bidirectional"))
    )
    (net (code "85") (name "unconnected-(U1A-PB15-Pad28)") (class "Default")
      (node (ref "U1") (pin "28") (pinfunction "PB15_28") (pintype "bidirectional"))
    )
    (net (code "86") (name "unconnected-(U1A-PC13-Pad2)") (class "Default")
      (node (ref "U1") (pin "2") (pinfunction "PC13_2") (pintype "bidirectional"))
    )
    (net (code "87") (name "unconnected-(U1A-PC14-OSC32_IN(PC14)-Pad3)") (class "Default")
      (node (ref "U1") (pin "3") (pinfunction "PC14-OSC32_IN(PC14)_3") (pintype "bidirectional"))
    )
    (net (code "88") (name "unconnected-(U1A-PC15-OSC32_OUT(PC15)-Pad4)") (class "Default")
      (node (ref "U1") (pin "4") (pinfunction "PC15-OSC32_OUT(PC15)_4") (pintype "bidirectional"))
    )
    (net (code "89") (name "unconnected-(U1A-PF6-Pad35)") (class "Default")
      (node (ref "U1") (pin "35") (pinfunction "PF6_35") (pintype "bidirectional"))
    )
    (net (code "90") (name "unconnected-(U1A-PF7-Pad36)") (class "Default")
      (node (ref "U1") (pin "36") (pinfunction "PF7_36") (pintype "bidirectional"))
    )
  )
)
